# STM32_Peripherals.net
KiCad netlist of a schematic drawn in Altium Designer
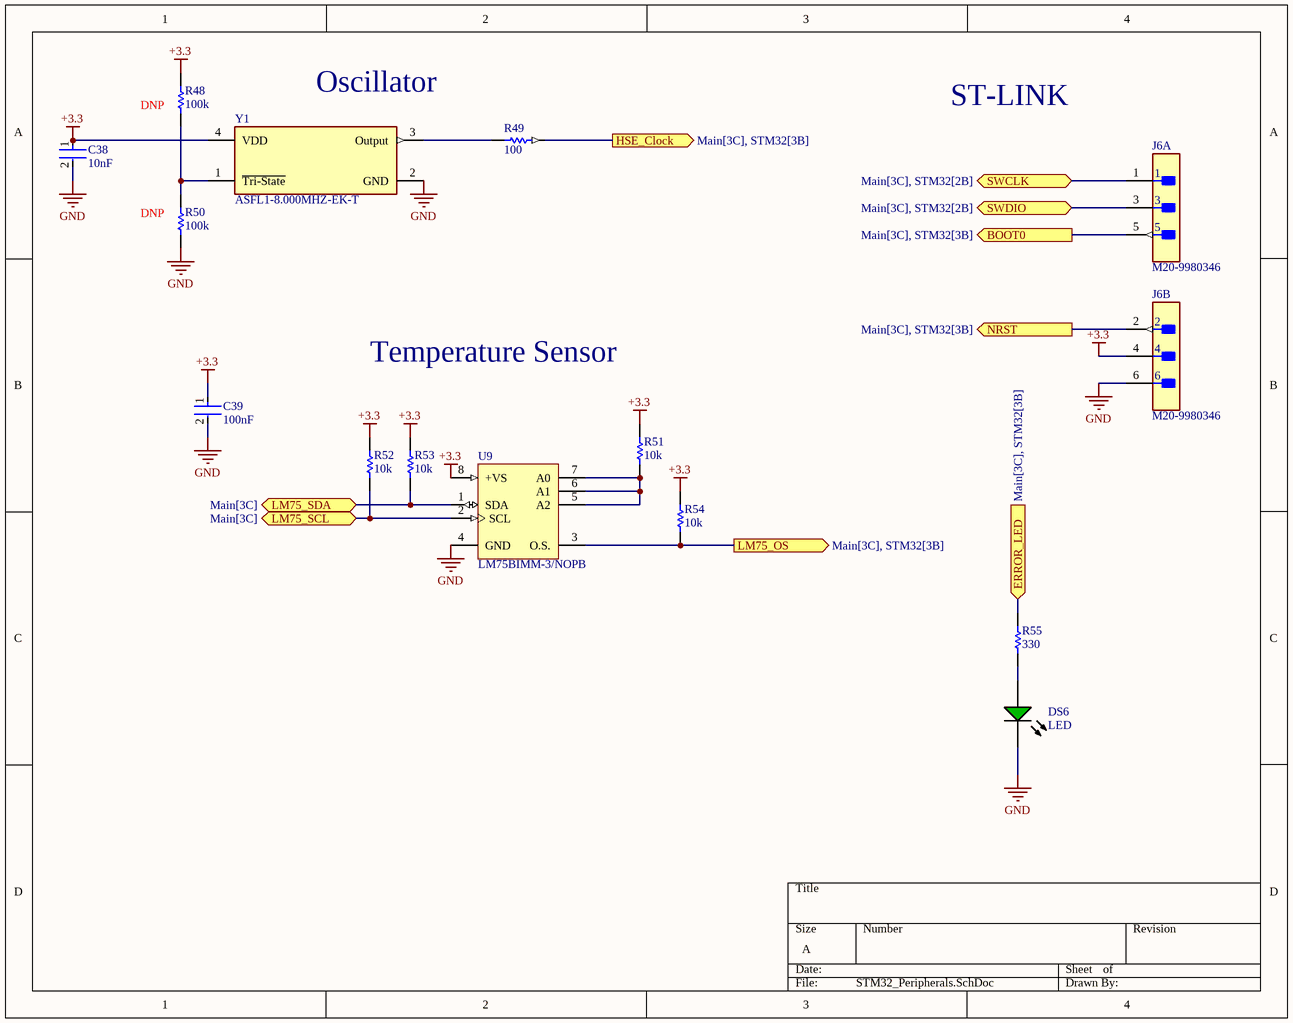
[diagram p0: STM32_Peripherals.SchDoc]

(export (version "E")
  (design (tool "Eeschema 10.0.6"))
  (components
    (comp (ref "C38")
      (value "10nF")
      (footprint "FP-0805-L_2_01_0_2-W_1_25-IPC_B")
      (description "General Purpose Ceramic Capacitor, 0805, 10nF, 10%, X7R, 15%, 100V")
      (fields (field (name "VOLTAGE") "100V") (field (name "TOLERANCE") "10%"))
      (libsource (lib "Altium Content Vault") (part "b4654b650e69147ec39a6b967a45e02"))
    )
    (comp (ref "C39")
      (value "100nF")
      (footprint "FP-0805-L_2_01_0_2-W_1_25-IPC_B")
      (description "General Purpose Ceramic Capacitor, 0805, 100nF, 10%, X7R, 15%, 100V")
      (fields (field (name "VOLTAGE") "100V") (field (name "TOLERANCE") "10%"))
      (libsource (lib "Altium Content Vault") (part "b4654b650e69147ec39a6b967a45e02"))
    )
    (comp (ref "DS6")
      (value "LED")
      (footprint "AVAG-HSMX-C170_V")
      (description "Chip LED, Green, 2.2 V, -40 to 85 degC, 2-Pin SMD, Pb-Free, Tape and Reel")
      (fields (field (name "MANUFACTURER") "Avago"))
      (libsource (lib "Altium Content Vault") (part "LED_GREEN_A1K2-2"))
    )
    (comp (ref "J6")
      (value "M20-9980346")
      (footprint "FP-M20-9980346-MFG")
      (description "CONN HEADER VERT 6POS 2.54MM")
      (fields
        (field (name "MANUFACTURER") "Harwin")
        (field (name "OCTOPART") "https://octopart.com/m20-9980346-harwin-5436545")
      )
      (libsource (lib "Altium Content Vault") (part "2654a11fb13586ecb194516b1c997bc"))
    )
    (comp (ref "R48")
      (value "100k")
      (footprint "RESC2013X50X30LL20T20")
      (fields (field (name "MANUFACTURER") "Vishay Dale") (field (name "PART NUMBER") "CRCW08050000Z0EA"))
      (libsource (lib "") (part "RES_1"))
    )
    (comp (ref "R49")
      (value "100")
      (footprint "RESC2013X50X30LL20T20")
      (fields (field (name "MANUFACTURER") "Vishay Dale") (field (name "PART NUMBER") "CRCW08050000Z0EA"))
      (libsource (lib "Altium Content Vault") (part "RES"))
    )
    (comp (ref "R50")
      (value "100k")
      (footprint "RESC2013X50X30LL20T20")
      (fields (field (name "MANUFACTURER") "Vishay Dale") (field (name "PART NUMBER") "CRCW08050000Z0EA"))
      (libsource (lib "") (part "RES_1"))
    )
    (comp (ref "R51")
      (value "10k")
      (footprint "RESC2013X50X30LL20T20")
      (fields (field (name "MANUFACTURER") "Vishay Dale") (field (name "PART NUMBER") "CRCW08050000Z0EA"))
      (libsource (lib "") (part "RES_1"))
    )
    (comp (ref "R52")
      (value "10k")
      (footprint "RESC2013X50X30LL20T20")
      (fields (field (name "MANUFACTURER") "Vishay Dale") (field (name "PART NUMBER") "CRCW08050000Z0EA"))
      (libsource (lib "") (part "RES_1"))
    )
    (comp (ref "R53")
      (value "10k")
      (footprint "RESC2013X50X30LL20T20")
      (fields (field (name "MANUFACTURER") "Vishay Dale") (field (name "PART NUMBER") "CRCW08050000Z0EA"))
      (libsource (lib "") (part "RES_1"))
    )
    (comp (ref "R54")
      (value "10k")
      (footprint "RESC2013X50X30LL20T20")
      (fields (field (name "MANUFACTURER") "Vishay Dale") (field (name "PART NUMBER") "CRCW08050000Z0EA"))
      (libsource (lib "") (part "RES_1"))
    )
    (comp (ref "R55")
      (value "330")
      (footprint "RESC2013X50X30LL20T20")
      (fields (field (name "MANUFACTURER") "Vishay Dale") (field (name "PART NUMBER") "CRCW08050000Z0EA"))
      (libsource (lib "") (part "RES_1"))
    )
    (comp (ref "U9")
      (value "LM75BIMM-3/NOPB")
      (footprint "DGK0008A_L")
      (description "Digital Temperature Sensor and Thermal Watchdog with Two-Wire Interface, 8-pin Mini SOIC, Pb-Free")
      (fields (field (name "MANUFACTURER") "Texas Instruments"))
      (libsource (lib "Altium Content Vault") (part "SEN-TEMP-LM75BIM-8"))
    )
    (comp (ref "Y1")
      (value "ASFL1-8.000MHZ-EK-T")
      (footprint "FP-ASFL1-MFG")
      (description "XTAL Oscillator 8MHz ±30ppm HCMOS, TTL 3.3V 4-SMD 5mm x 3.2mm")
      (libsource (lib "Altium Content Vault") (part "47df00dc2349451232cb22fac08fbff"))
    )
  )
  (nets
    (net (code "1") (name "+3.3") (class "Default")
      (node (ref "C38") (pin "1") (pinfunction "1_1") (pintype "passive"))
      (node (ref "C39") (pin "1") (pinfunction "1_1") (pintype "passive"))
      (node (ref "J6") (pin "4") (pinfunction "4_4") (pintype "passive"))
      (node (ref "R48") (pin "2") (pinfunction "2_2") (pintype "passive"))
      (node (ref "R51") (pin "2") (pinfunction "2_2") (pintype "passive"))
      (node (ref "R52") (pin "2") (pinfunction "2_2") (pintype "passive"))
      (node (ref "R53") (pin "2") (pinfunction "2_2") (pintype "passive"))
      (node (ref "R54") (pin "2") (pinfunction "2_2") (pintype "passive"))
      (node (ref "U9") (pin "8") (pinfunction "+VS_8") (pintype "input"))
      (node (ref "Y1") (pin "4") (pinfunction "VDD_4") (pintype "power_in"))
    )
    (net (code "3") (name "/BOOT0") (class "Default")
      (node (ref "J6") (pin "5") (pinfunction "5_5") (pintype "passive"))
    )
    (net (code "4") (name "/ERROR_LED") (class "Default")
      (node (ref "R55") (pin "2") (pinfunction "2_2") (pintype "passive"))
    )
    (net (code "5") (name "/HSE_Clock") (class "Default")
      (node (ref "R49") (pin "2") (pinfunction "2_2") (pintype "output"))
    )
    (net (code "6") (name "/LM75_OS") (class "Default")
      (node (ref "R54") (pin "1") (pinfunction "1_1") (pintype "passive"))
      (node (ref "U9") (pin "3") (pinfunction "O.S._3") (pintype "open_collector"))
    )
    (net (code "7") (name "/LM75_SCL") (class "Default")
      (node (ref "R52") (pin "1") (pinfunction "1_1") (pintype "passive"))
      (node (ref "U9") (pin "2") (pinfunction "SCL_2") (pintype "input"))
    )
    (net (code "8") (name "/LM75_SDA") (class "Default")
      (node (ref "R53") (pin "1") (pinfunction "1_1") (pintype "passive"))
      (node (ref "U9") (pin "1") (pinfunction "SDA_1") (pintype "bidirectional"))
    )
    (net (code "9") (name "/NRST") (class "Default")
      (node (ref "J6") (pin "2") (pinfunction "2_2") (pintype "output"))
    )
    (net (code "10") (name "/SWCLK") (class "Default")
      (node (ref "J6") (pin "1") (pinfunction "1_1") (pintype "passive"))
    )
    (net (code "11") (name "/SWDIO") (class "Default")
      (node (ref "J6") (pin "3") (pinfunction "3_3") (pintype "passive"))
    )
    (net (code "12") (name "GND") (class "Default")
      (node (ref "C38") (pin "2") (pinfunction "2_2") (pintype "passive"))
      (node (ref "C39") (pin "2") (pinfunction "2_2") (pintype "passive"))
      (node (ref "DS6") (pin "2") (pinfunction "K_2") (pintype "passive"))
      (node (ref "J6") (pin "6") (pinfunction "6_6") (pintype "passive"))
      (node (ref "R50") (pin "1") (pinfunction "1_1") (pintype "passive"))
      (node (ref "U9") (pin "4") (pinfunction "GND_4") (pintype "power_in"))
      (node (ref "Y1") (pin "2") (pinfunction "GND_2") (pintype "power_in"))
    )
    (net (code "13") (name "Net-(DS6-A)") (class "Default")
      (node (ref "DS6") (pin "1") (pinfunction "A_1") (pintype "passive"))
      (node (ref "R55") (pin "1") (pinfunction "1_1") (pintype "passive"))
    )
    (net (code "14") (name "Net-(U9-A0)") (class "Default")
      (node (ref "R51") (pin "1") (pinfunction "1_1") (pintype "passive"))
      (node (ref "U9") (pin "5") (pinfunction "A2_5") (pintype "passive"))
      (node (ref "U9") (pin "6") (pinfunction "A1_6") (pintype "passive"))
      (node (ref "U9") (pin "7") (pinfunction "A0_7") (pintype "passive"))
    )
    (net (code "15") (name "Net-(Y1-Output)") (class "Default")
      (node (ref "R49") (pin "1") (pinfunction "1_1") (pintype "passive"))
      (node (ref "Y1") (pin "3") (pinfunction "Output_3") (pintype "output"))
    )
    (net (code "16") (name "Net-(Y1-~{Tri-State})") (class "Default")
      (node (ref "R48") (pin "1") (pinfunction "1_1") (pintype "passive"))
      (node (ref "R50") (pin "2") (pinfunction "2_2") (pintype "passive"))
      (node (ref "Y1") (pin "1") (pinfunction "~{Tri-State}_1") (pintype "passive"))
    )
  )
)
